# Sheet1.net
KiCad netlist of a schematic drawn in Altium Designer
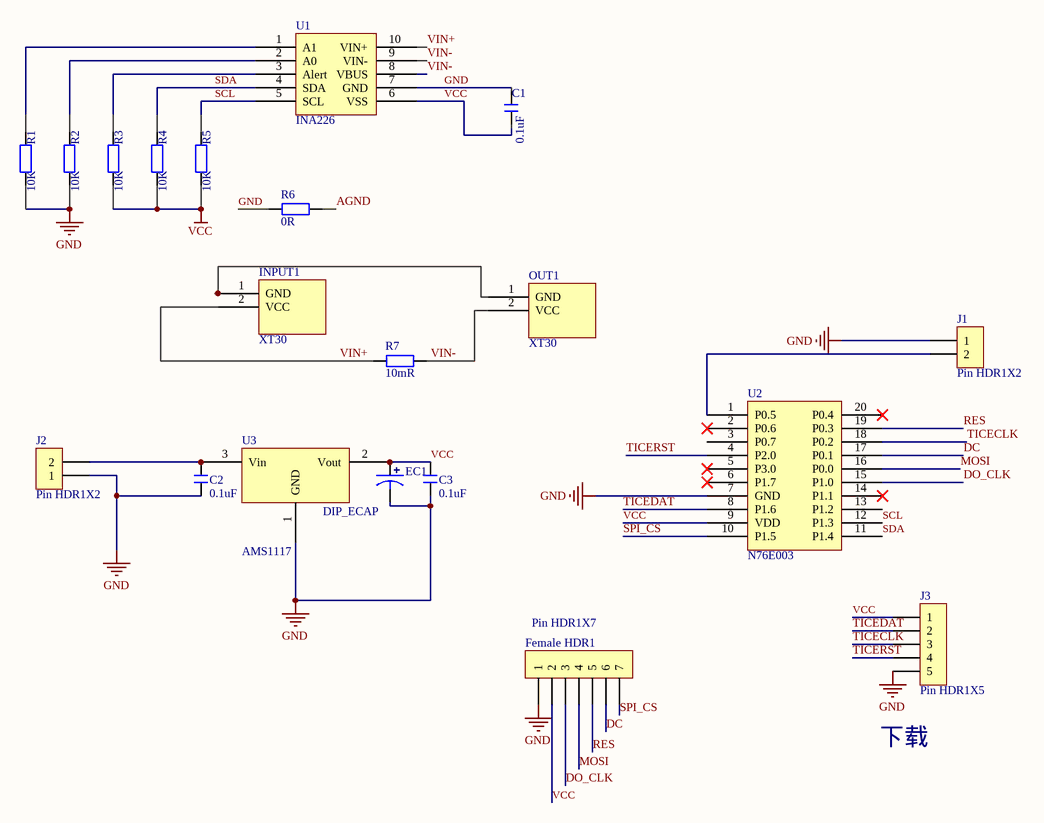
[diagram p0: Sheet1.SchDoc]

(export (version "E")
  (design (tool "Eeschema 10.0.6"))
  (components
    (comp (ref "C1")
      (value "0.1uF")
      (footprint "C 0603_L")
      (description "贴片电容")
      (libsource (lib "0.1 - 电阻-电容-电感") (part "C"))
    )
    (comp (ref "C2")
      (value "0.1uF")
      (footprint "0805C")
      (description "贴片电容")
      (libsource (lib "0.1 - 电阻-电容-电感") (part "C"))
    )
    (comp (ref "C3")
      (value "0.1uF")
      (footprint "0805C")
      (description "贴片电容")
      (libsource (lib "0.1 - 电阻-电容-电感") (part "C"))
    )
    (comp (ref "EC1")
      (value "DIP_ECAP")
      (footprint "DIP-EC2.5X6.3X11.2")
      (description "直插电解电容")
      (libsource (lib "电容") (part "DIP_ECAP"))
    )
    (comp (ref "Female HDR1")
      (value "Pin HDR1X7")
      (footprint "Pin HDR1X7/2.54mm-S")
      (libsource (lib "排针") (part "Pin HDR1X7"))
    )
    (comp (ref "INPUT1") (value "XT30") (footprint "XT30") (libsource (lib "PCB_Project") (part "XT30")))
    (comp (ref "J1")
      (value "Pin HDR1X2")
      (footprint "Pin HDR1X2/2.54mm-S")
      (libsource (lib "") (part "Pin HDR1X2_1"))
    )
    (comp (ref "J2")
      (value "Pin HDR1X2")
      (footprint "Pin HDR1X2/2.54mm-S")
      (libsource (lib "排针") (part "Pin HDR1X2"))
    )
    (comp (ref "J3")
      (value "Pin HDR1X5")
      (footprint "Pin HDR1X5/2.54mm-S")
      (libsource (lib "排针") (part "Pin HDR1X5"))
    )
    (comp (ref "OUT1") (value "XT30") (footprint "XT30") (libsource (lib "PCB_Project") (part "XT30")))
    (comp (ref "R1")
      (value "10K")
      (footprint "R 0603_L")
      (description "贴片电阻")
      (fields (field (name "版权归属") "来自淘宝 ID：黄晶宝石"))
      (libsource (lib "0.1 - 电阻-电容-电感") (part "R"))
    )
    (comp (ref "R2")
      (value "10K")
      (footprint "R 0603_L")
      (description "贴片电阻")
      (fields (field (name "版权归属") "来自淘宝 ID：黄晶宝石"))
      (libsource (lib "0.1 - 电阻-电容-电感") (part "R"))
    )
    (comp (ref "R3")
      (value "10K")
      (footprint "R 0603_L")
      (description "贴片电阻")
      (fields (field (name "版权归属") "来自淘宝 ID：黄晶宝石"))
      (libsource (lib "0.1 - 电阻-电容-电感") (part "R"))
    )
    (comp (ref "R4")
      (value "10K")
      (footprint "R 0603_L")
      (description "贴片电阻")
      (fields (field (name "版权归属") "来自淘宝 ID：黄晶宝石"))
      (libsource (lib "0.1 - 电阻-电容-电感") (part "R"))
    )
    (comp (ref "R5")
      (value "10K")
      (footprint "R 0603_L")
      (description "贴片电阻")
      (fields (field (name "版权归属") "来自淘宝 ID：黄晶宝石"))
      (libsource (lib "0.1 - 电阻-电容-电感") (part "R"))
    )
    (comp (ref "R6")
      (value "0R")
      (footprint "R 0805_L")
      (description "贴片电阻")
      (fields (field (name "版权归属") "来自淘宝 ID：黄晶宝石"))
      (libsource (lib "0.1 - 电阻-电容-电感") (part "R"))
    )
    (comp (ref "R7")
      (value "10mR")
      (footprint "R 2512_L")
      (description "贴片电阻")
      (fields (field (name "版权归属") "来自淘宝 ID：黄晶宝石"))
      (libsource (lib "0.1 - 电阻-电容-电感") (part "R"))
    )
    (comp (ref "U1") (value "INA226") (footprint "MSOP-10") (libsource (lib "Schlib1") (part "ina226")))
    (comp (ref "U2")
      (value "N76E003")
      (footprint "N76E003-20N")
      (libsource (lib "mySchLib") (part "N76E003"))
    )
    (comp (ref "U3")
      (value "AMS1117")
      (footprint "SOT223")
      (description "三端稳压芯片")
      (libsource (lib "电源芯片") (part "AMS1117"))
    )
  )
  (nets
    (net (code "1") (name "/AGND") (class "Default")
      (node (ref "R6") (pin "1") (pinfunction "1_1") (pintype "passive"))
    )
    (net (code "2") (name "/DC") (class "Default")
      (node (ref "Female HDR1") (pin "6") (pinfunction "6_6") (pintype "passive"))
      (node (ref "U2") (pin "17") (pinfunction "P0.1_17") (pintype "passive"))
    )
    (net (code "3") (name "/DO_CLK") (class "Default")
      (node (ref "Female HDR1") (pin "3") (pinfunction "3_3") (pintype "passive"))
      (node (ref "U2") (pin "15") (pinfunction "P1.0_15") (pintype "passive"))
    )
    (net (code "4") (name "/MOSI") (class "Default")
      (node (ref "Female HDR1") (pin "4") (pinfunction "4_4") (pintype "passive"))
      (node (ref "U2") (pin "16") (pinfunction "P0.0_16") (pintype "passive"))
    )
    (net (code "5") (name "/RES") (class "Default")
      (node (ref "Female HDR1") (pin "5") (pinfunction "5_5") (pintype "passive"))
      (node (ref "U2") (pin "19") (pinfunction "P0.3_19") (pintype "passive"))
    )
    (net (code "6") (name "/SCL") (class "Default")
      (node (ref "R5") (pin "2") (pinfunction "2_2") (pintype "passive"))
      (node (ref "U1") (pin "5") (pinfunction "SCL_5") (pintype "passive"))
      (node (ref "U2") (pin "12") (pinfunction "P1.3_12") (pintype "passive"))
    )
    (net (code "7") (name "/SDA") (class "Default")
      (node (ref "R4") (pin "2") (pinfunction "2_2") (pintype "passive"))
      (node (ref "U1") (pin "4") (pinfunction "SDA_4") (pintype "passive"))
      (node (ref "U2") (pin "11") (pinfunction "P1.4_11") (pintype "passive"))
    )
    (net (code "8") (name "/SPI_CS") (class "Default")
      (node (ref "Female HDR1") (pin "7") (pinfunction "7_7") (pintype "passive"))
      (node (ref "U2") (pin "10") (pinfunction "P1.5_10") (pintype "passive"))
    )
    (net (code "9") (name "/TICECLK") (class "Default")
      (node (ref "J3") (pin "3") (pinfunction "3_3") (pintype "passive"))
      (node (ref "U2") (pin "18") (pinfunction "P0.2_18") (pintype "passive"))
    )
    (net (code "10") (name "/TICEDAT") (class "Default")
      (node (ref "J3") (pin "2") (pinfunction "2_2") (pintype "passive"))
      (node (ref "U2") (pin "8") (pinfunction "P1.6_8") (pintype "passive"))
    )
    (net (code "11") (name "/TICERST") (class "Default")
      (node (ref "J3") (pin "4") (pinfunction "4_4") (pintype "passive"))
      (node (ref "U2") (pin "4") (pinfunction "P2.0_4") (pintype "passive"))
    )
    (net (code "12") (name "/VIN+") (class "Default")
      (node (ref "INPUT1") (pin "2") (pinfunction "VCC_2") (pintype "passive"))
      (node (ref "R7") (pin "1") (pinfunction "1_1") (pintype "passive"))
      (node (ref "U1") (pin "10") (pinfunction "VIN+_10") (pintype "passive"))
    )
    (net (code "13") (name "/VIN-") (class "Default")
      (node (ref "OUT1") (pin "2") (pinfunction "VCC_2") (pintype "passive"))
      (node (ref "R7") (pin "2") (pinfunction "2_2") (pintype "passive"))
      (node (ref "U1") (pin "8") (pinfunction "VBUS_8") (pintype "passive"))
      (node (ref "U1") (pin "9") (pinfunction "VIN-_9") (pintype "passive"))
    )
    (net (code "14") (name "GND") (class "Default")
      (node (ref "C1") (pin "2") (pinfunction "2_2") (pintype "passive"))
      (node (ref "C2") (pin "2") (pinfunction "2_2") (pintype "passive"))
      (node (ref "C3") (pin "2") (pinfunction "2_2") (pintype "passive"))
      (node (ref "EC1") (pin "2") (pinfunction "2_2") (pintype "passive"))
      (node (ref "Female HDR1") (pin "1") (pinfunction "1_1") (pintype "passive"))
      (node (ref "J1") (pin "1") (pinfunction "1_1") (pintype "passive"))
      (node (ref "J2") (pin "1") (pinfunction "1_1") (pintype "passive"))
      (node (ref "J3") (pin "5") (pinfunction "5_5") (pintype "passive"))
      (node (ref "R1") (pin "1") (pinfunction "1_1") (pintype "passive"))
      (node (ref "R2") (pin "1") (pinfunction "1_1") (pintype "passive"))
      (node (ref "R6") (pin "2") (pinfunction "2_2") (pintype "passive"))
      (node (ref "U1") (pin "7") (pinfunction "GND_7") (pintype "passive"))
      (node (ref "U2") (pin "7") (pinfunction "GND_7") (pintype "passive"))
      (node (ref "U3") (pin "1") (pinfunction "GND_1") (pintype "passive"))
    )
    (net (code "15") (name "Net-(INPUT1-GND)") (class "Default")
      (node (ref "INPUT1") (pin "1") (pinfunction "GND_1") (pintype "passive"))
      (node (ref "OUT1") (pin "1") (pinfunction "GND_1") (pintype "passive"))
    )
    (net (code "16") (name "Net-(U1-A0)") (class "Default")
      (node (ref "R2") (pin "2") (pinfunction "2_2") (pintype "passive"))
      (node (ref "U1") (pin "2") (pinfunction "A0_2") (pintype "passive"))
    )
    (net (code "17") (name "Net-(U1-A1)") (class "Default")
      (node (ref "R1") (pin "2") (pinfunction "2_2") (pintype "passive"))
      (node (ref "U1") (pin "1") (pinfunction "A1_1") (pintype "passive"))
    )
    (net (code "18") (name "Net-(U1-Alert)") (class "Default")
      (node (ref "R3") (pin "2") (pinfunction "2_2") (pintype "passive"))
      (node (ref "U1") (pin "3") (pinfunction "Alert_3") (pintype "passive"))
    )
    (net (code "19") (name "Net-(U2-P0.5)") (class "Default")
      (node (ref "J1") (pin "2") (pinfunction "2_2") (pintype "passive"))
      (node (ref "U2") (pin "1") (pinfunction "P0.5_1") (pintype "passive"))
    )
    (net (code "20") (name "Net-(U3-Vin)") (class "Default")
      (node (ref "C2") (pin "1") (pinfunction "1_1") (pintype "passive"))
      (node (ref "J2") (pin "2") (pinfunction "2_2") (pintype "passive"))
      (node (ref "U3") (pin "3") (pinfunction "Vin_3") (pintype "passive"))
    )
    (net (code "21") (name "VCC") (class "Default")
      (node (ref "C1") (pin "1") (pinfunction "1_1") (pintype "passive"))
      (node (ref "C3") (pin "1") (pinfunction "1_1") (pintype "passive"))
      (node (ref "EC1") (pin "1") (pinfunction "1_1") (pintype "passive"))
      (node (ref "Female HDR1") (pin "2") (pinfunction "2_2") (pintype "passive"))
      (node (ref "J3") (pin "1") (pinfunction "1_1") (pintype "passive"))
      (node (ref "R3") (pin "1") (pinfunction "1_1") (pintype "passive"))
      (node (ref "R4") (pin "1") (pinfunction "1_1") (pintype "passive"))
      (node (ref "R5") (pin "1") (pinfunction "1_1") (pintype "passive"))
      (node (ref "U1") (pin "6") (pinfunction "VSS_6") (pintype "passive"))
      (node (ref "U2") (pin "9") (pinfunction "VDD_9") (pintype "passive"))
      (node (ref "U3") (pin "2") (pinfunction "Vout_2") (pintype "passive"))
    )
    (net (code "22") (name "unconnected-(U2-P0.4-Pad20)") (class "Default")
      (node (ref "U2") (pin "20") (pinfunction "P0.4_20") (pintype "passive+no_connect"))
    )
    (net (code "23") (name "unconnected-(U2-P0.6-Pad2)") (class "Default")
      (node (ref "U2") (pin "2") (pinfunction "P0.6_2") (pintype "passive+no_connect"))
    )
    (net (code "24") (name "unconnected-(U2-P0.7-Pad3)") (class "Default")
      (node (ref "U2") (pin "3") (pinfunction "P0.7_3") (pintype "passive"))
    )
    (net (code "25") (name "unconnected-(U2-P1.1-Pad14)") (class "Default")
      (node (ref "U2") (pin "14") (pinfunction "P1.1_14") (pintype "passive+no_connect"))
    )
    (net (code "26") (name "unconnected-(U2-P1.2-Pad13)") (class "Default")
      (node (ref "U2") (pin "13") (pinfunction "P1.2_13") (pintype "passive"))
    )
    (net (code "27") (name "unconnected-(U2-P1.7-Pad6)") (class "Default")
      (node (ref "U2") (pin "6") (pinfunction "P1.7_6") (pintype "passive+no_connect"))
    )
    (net (code "28") (name "unconnected-(U2-P3.0-Pad5)") (class "Default")
      (node (ref "U2") (pin "5") (pinfunction "P3.0_5") (pintype "passive+no_connect"))
    )
  )
)
